# 7474-strobe-generator-v3.net
KiCad netlist of a schematic drawn in EAGLE
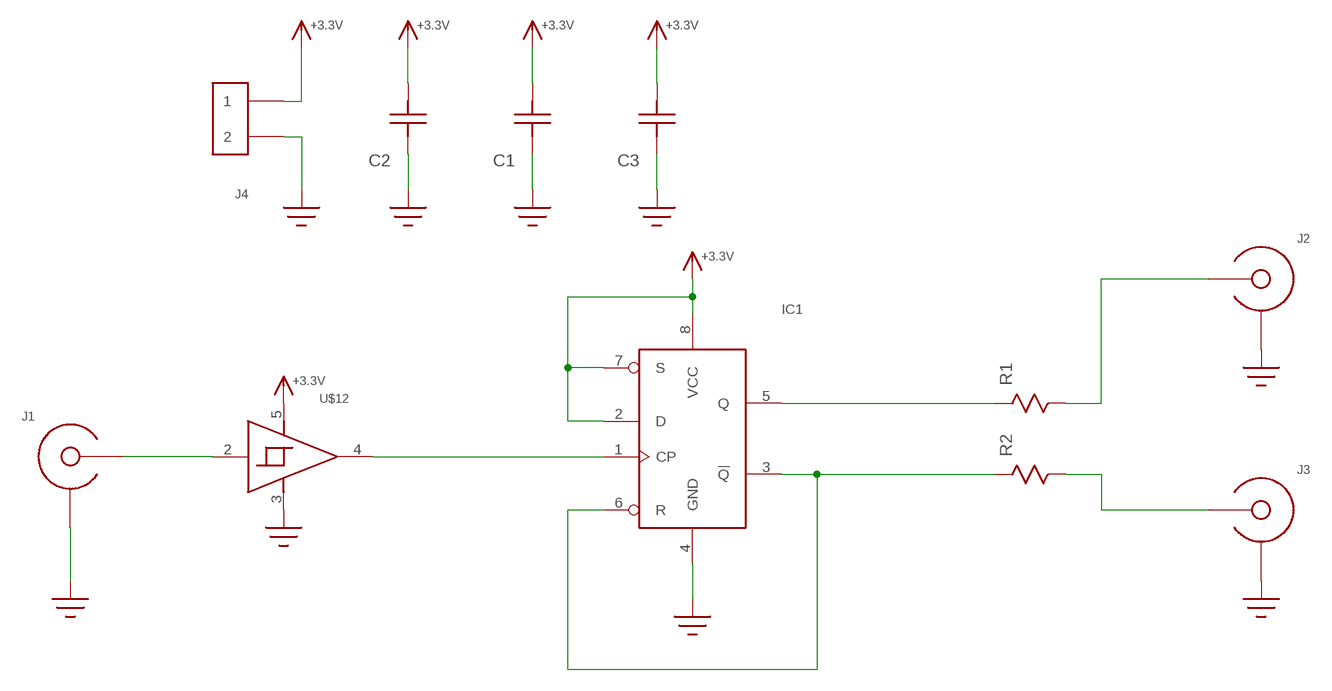
[diagram p0: schematic, sheet 1]

(export (version "E")
  (design (tool "Eeschema 10.0.6"))
  (components
    (comp (ref "C1")
      (value "C0603")
      (footprint "eagle-import:C0603")
      (libsource (lib "eagle-import") (part "C0603"))
    )
    (comp (ref "C2")
      (value "C1206")
      (footprint "eagle-import:1206")
      (libsource (lib "eagle-import") (part "C1206"))
    )
    (comp (ref "C3")
      (value "C0603")
      (footprint "eagle-import:C0603")
      (libsource (lib "eagle-import") (part "C0603"))
    )
    (comp (ref "IC1")
      (value "74LVC2G74")
      (footprint "eagle-import:SSOP8")
      (libsource (lib "eagle-import") (part "74LVC2G74"))
    )
    (comp (ref "J1")
      (value "SMA-EDGE-LAUNCH4020_TAPER")
      (footprint "eagle-import:SMA_EDGE_LAUNCH_2L_4020_TAPER")
      (libsource (lib "eagle-import") (part "SMA-EDGE-LAUNCH4020_TAPER"))
    )
    (comp (ref "J2")
      (value "SMA-EDGE-LAUNCH4020_TAPER")
      (footprint "eagle-import:SMA_EDGE_LAUNCH_2L_4020_TAPER")
      (libsource (lib "eagle-import") (part "SMA-EDGE-LAUNCH4020_TAPER"))
    )
    (comp (ref "J3")
      (value "SMA-EDGE-LAUNCH4020_TAPER")
      (footprint "eagle-import:SMA_EDGE_LAUNCH_2L_4020_TAPER")
      (libsource (lib "eagle-import") (part "SMA-EDGE-LAUNCH4020_TAPER"))
    )
    (comp (ref "J4")
      (value "HEADER_2PIN")
      (footprint "eagle-import:HEADER_2PIN")
      (libsource (lib "eagle-import") (part "HEADER_2PIN"))
    )
    (comp (ref "R1")
      (value "R0603")
      (footprint "eagle-import:R0603")
      (libsource (lib "eagle-import") (part "R0603"))
    )
    (comp (ref "R2")
      (value "R0603")
      (footprint "eagle-import:R0603")
      (libsource (lib "eagle-import") (part "R0603"))
    )
    (comp (ref "U$12")
      (value "74LVC1G17")
      (footprint "eagle-import:SOT23-5")
      (libsource (lib "eagle-import") (part "74LVC1G17"))
    )
  )
  (nets
    (net (code "1") (name "+3.3V") (class "Default")
      (node (ref "C1") (pin "P$1") (pinfunction "P$1_P$1") (pintype "bidirectional"))
      (node (ref "C2") (pin "P$1") (pinfunction "P$1_P$1") (pintype "bidirectional"))
      (node (ref "C3") (pin "P$1") (pinfunction "P$1_P$1") (pintype "bidirectional"))
      (node (ref "IC1") (pin "2") (pinfunction "D_2") (pintype "bidirectional"))
      (node (ref "IC1") (pin "7") (pinfunction "S_7") (pintype "bidirectional"))
      (node (ref "IC1") (pin "8") (pinfunction "VCC_8") (pintype "bidirectional"))
      (node (ref "J4") (pin "1") (pinfunction "1_1") (pintype "bidirectional"))
      (node (ref "U$12") (pin "5") (pinfunction "VCC_5") (pintype "bidirectional"))
    )
    (net (code "2") (name "GND") (class "Default")
      (node (ref "C1") (pin "P$2") (pinfunction "P$2_P$2") (pintype "bidirectional"))
      (node (ref "C2") (pin "P$2") (pinfunction "P$2_P$2") (pintype "bidirectional"))
      (node (ref "C3") (pin "P$2") (pinfunction "P$2_P$2") (pintype "bidirectional"))
      (node (ref "IC1") (pin "4") (pinfunction "GND_4") (pintype "bidirectional"))
      (node (ref "J1") (pin "BOTTOM_GND") (pinfunction "SHIELD_BOTTOM_GND") (pintype "bidirectional"))
      (node (ref "J1") (pin "GND@1") (pinfunction "SHIELD_GND@1") (pintype "bidirectional"))
      (node (ref "J1") (pin "GND@14") (pinfunction "SHIELD_GND@14") (pintype "bidirectional"))
      (node (ref "J1") (pin "GND@15") (pinfunction "SHIELD_GND@15") (pintype "bidirectional"))
      (node (ref "J1") (pin "GND@16") (pinfunction "SHIELD_GND@16") (pintype "bidirectional"))
      (node (ref "J1") (pin "GND@17") (pinfunction "SHIELD_GND@17") (pintype "bidirectional"))
      (node (ref "J1") (pin "GND@2") (pinfunction "SHIELD_GND@2") (pintype "bidirectional"))
      (node (ref "J1") (pin "GND@3") (pinfunction "SHIELD_GND@3") (pintype "bidirectional"))
      (node (ref "J1") (pin "GND@4") (pinfunction "SHIELD_GND@4") (pintype "bidirectional"))
      (node (ref "J1") (pin "GND@5") (pinfunction "SHIELD_GND@5") (pintype "bidirectional"))
      (node (ref "J1") (pin "GND@6") (pinfunction "SHIELD_GND@6") (pintype "bidirectional"))
      (node (ref "J1") (pin "GND@7") (pinfunction "SHIELD_GND@7") (pintype "bidirectional"))
      (node (ref "J1") (pin "GND@8") (pinfunction "SHIELD_GND@8") (pintype "bidirectional"))
      (node (ref "J1") (pin "GND_PAD1") (pinfunction "SHIELD_GND_PAD1") (pintype "bidirectional"))
      (node (ref "J1") (pin "GND_PAD2") (pinfunction "SHIELD_GND_PAD2") (pintype "bidirectional"))
      (node (ref "J1") (pin "P$1") (pinfunction "SHIELD_P$1") (pintype "bidirectional"))
      (node (ref "J1") (pin "P$2") (pinfunction "SHIELD_P$2") (pintype "bidirectional"))
      (node (ref "J2") (pin "BOTTOM_GND") (pinfunction "SHIELD_BOTTOM_GND") (pintype "bidirectional"))
      (node (ref "J2") (pin "GND@1") (pinfunction "SHIELD_GND@1") (pintype "bidirectional"))
      (node (ref "J2") (pin "GND@14") (pinfunction "SHIELD_GND@14") (pintype "bidirectional"))
      (node (ref "J2") (pin "GND@15") (pinfunction "SHIELD_GND@15") (pintype "bidirectional"))
      (node (ref "J2") (pin "GND@16") (pinfunction "SHIELD_GND@16") (pintype "bidirectional"))
      (node (ref "J2") (pin "GND@17") (pinfunction "SHIELD_GND@17") (pintype "bidirectional"))
      (node (ref "J2") (pin "GND@2") (pinfunction "SHIELD_GND@2") (pintype "bidirectional"))
      (node (ref "J2") (pin "GND@3") (pinfunction "SHIELD_GND@3") (pintype "bidirectional"))
      (node (ref "J2") (pin "GND@4") (pinfunction "SHIELD_GND@4") (pintype "bidirectional"))
      (node (ref "J2") (pin "GND@5") (pinfunction "SHIELD_GND@5") (pintype "bidirectional"))
      (node (ref "J2") (pin "GND@6") (pinfunction "SHIELD_GND@6") (pintype "bidirectional"))
      (node (ref "J2") (pin "GND@7") (pinfunction "SHIELD_GND@7") (pintype "bidirectional"))
      (node (ref "J2") (pin "GND@8") (pinfunction "SHIELD_GND@8") (pintype "bidirectional"))
      (node (ref "J2") (pin "GND_PAD1") (pinfunction "SHIELD_GND_PAD1") (pintype "bidirectional"))
      (node (ref "J2") (pin "GND_PAD2") (pinfunction "SHIELD_GND_PAD2") (pintype "bidirectional"))
      (node (ref "J2") (pin "P$1") (pinfunction "SHIELD_P$1") (pintype "bidirectional"))
      (node (ref "J2") (pin "P$2") (pinfunction "SHIELD_P$2") (pintype "bidirectional"))
      (node (ref "J3") (pin "BOTTOM_GND") (pinfunction "SHIELD_BOTTOM_GND") (pintype "bidirectional"))
      (node (ref "J3") (pin "GND@1") (pinfunction "SHIELD_GND@1") (pintype "bidirectional"))
      (node (ref "J3") (pin "GND@14") (pinfunction "SHIELD_GND@14") (pintype "bidirectional"))
      (node (ref "J3") (pin "GND@15") (pinfunction "SHIELD_GND@15") (pintype "bidirectional"))
      (node (ref "J3") (pin "GND@16") (pinfunction "SHIELD_GND@16") (pintype "bidirectional"))
      (node (ref "J3") (pin "GND@17") (pinfunction "SHIELD_GND@17") (pintype "bidirectional"))
      (node (ref "J3") (pin "GND@2") (pinfunction "SHIELD_GND@2") (pintype "bidirectional"))
      (node (ref "J3") (pin "GND@3") (pinfunction "SHIELD_GND@3") (pintype "bidirectional"))
      (node (ref "J3") (pin "GND@4") (pinfunction "SHIELD_GND@4") (pintype "bidirectional"))
      (node (ref "J3") (pin "GND@5") (pinfunction "SHIELD_GND@5") (pintype "bidirectional"))
      (node (ref "J3") (pin "GND@6") (pinfunction "SHIELD_GND@6") (pintype "bidirectional"))
      (node (ref "J3") (pin "GND@7") (pinfunction "SHIELD_GND@7") (pintype "bidirectional"))
      (node (ref "J3") (pin "GND@8") (pinfunction "SHIELD_GND@8") (pintype "bidirectional"))
      (node (ref "J3") (pin "GND_PAD1") (pinfunction "SHIELD_GND_PAD1") (pintype "bidirectional"))
      (node (ref "J3") (pin "GND_PAD2") (pinfunction "SHIELD_GND_PAD2") (pintype "bidirectional"))
      (node (ref "J3") (pin "P$1") (pinfunction "SHIELD_P$1") (pintype "bidirectional"))
      (node (ref "J3") (pin "P$2") (pinfunction "SHIELD_P$2") (pintype "bidirectional"))
      (node (ref "J4") (pin "2") (pinfunction "2_2") (pintype "bidirectional"))
      (node (ref "U$12") (pin "3") (pinfunction "GND_3") (pintype "bidirectional"))
    )
    (net (code "3") (name "Net-(IC1-CP)") (class "Default")
      (node (ref "IC1") (pin "1") (pinfunction "CP_1") (pintype "bidirectional"))
      (node (ref "U$12") (pin "4") (pinfunction "OUT_4") (pintype "bidirectional"))
    )
    (net (code "4") (name "Net-(IC1-Q)") (class "Default")
      (node (ref "IC1") (pin "5") (pinfunction "Q_5") (pintype "bidirectional"))
      (node (ref "R1") (pin "P$1") (pinfunction "P$3_P$1") (pintype "bidirectional"))
    )
    (net (code "5") (name "Net-(IC1-R)") (class "Default")
      (node (ref "IC1") (pin "3") (pinfunction "~{Q}_3") (pintype "bidirectional"))
      (node (ref "IC1") (pin "6") (pinfunction "R_6") (pintype "bidirectional"))
      (node (ref "R2") (pin "P$1") (pinfunction "P$3_P$1") (pintype "bidirectional"))
    )
    (net (code "6") (name "Net-(J1-CENTER)") (class "Default")
      (node (ref "J1") (pin "CENTER@1") (pinfunction "CENTER_CENTER@1") (pintype "bidirectional"))
      (node (ref "U$12") (pin "2") (pinfunction "IN_2") (pintype "bidirectional"))
    )
    (net (code "7") (name "Net-(J2-CENTER)") (class "Default")
      (node (ref "J2") (pin "CENTER@1") (pinfunction "CENTER_CENTER@1") (pintype "bidirectional"))
      (node (ref "R1") (pin "P$2") (pinfunction "P$4_P$2") (pintype "bidirectional"))
    )
    (net (code "8") (name "Net-(J3-CENTER)") (class "Default")
      (node (ref "J3") (pin "CENTER@1") (pinfunction "CENTER_CENTER@1") (pintype "bidirectional"))
      (node (ref "R2") (pin "P$2") (pinfunction "P$4_P$2") (pintype "bidirectional"))
    )
  )
)
